# CH382CRD.net
KiCad netlist of a schematic drawn in Altium Designer
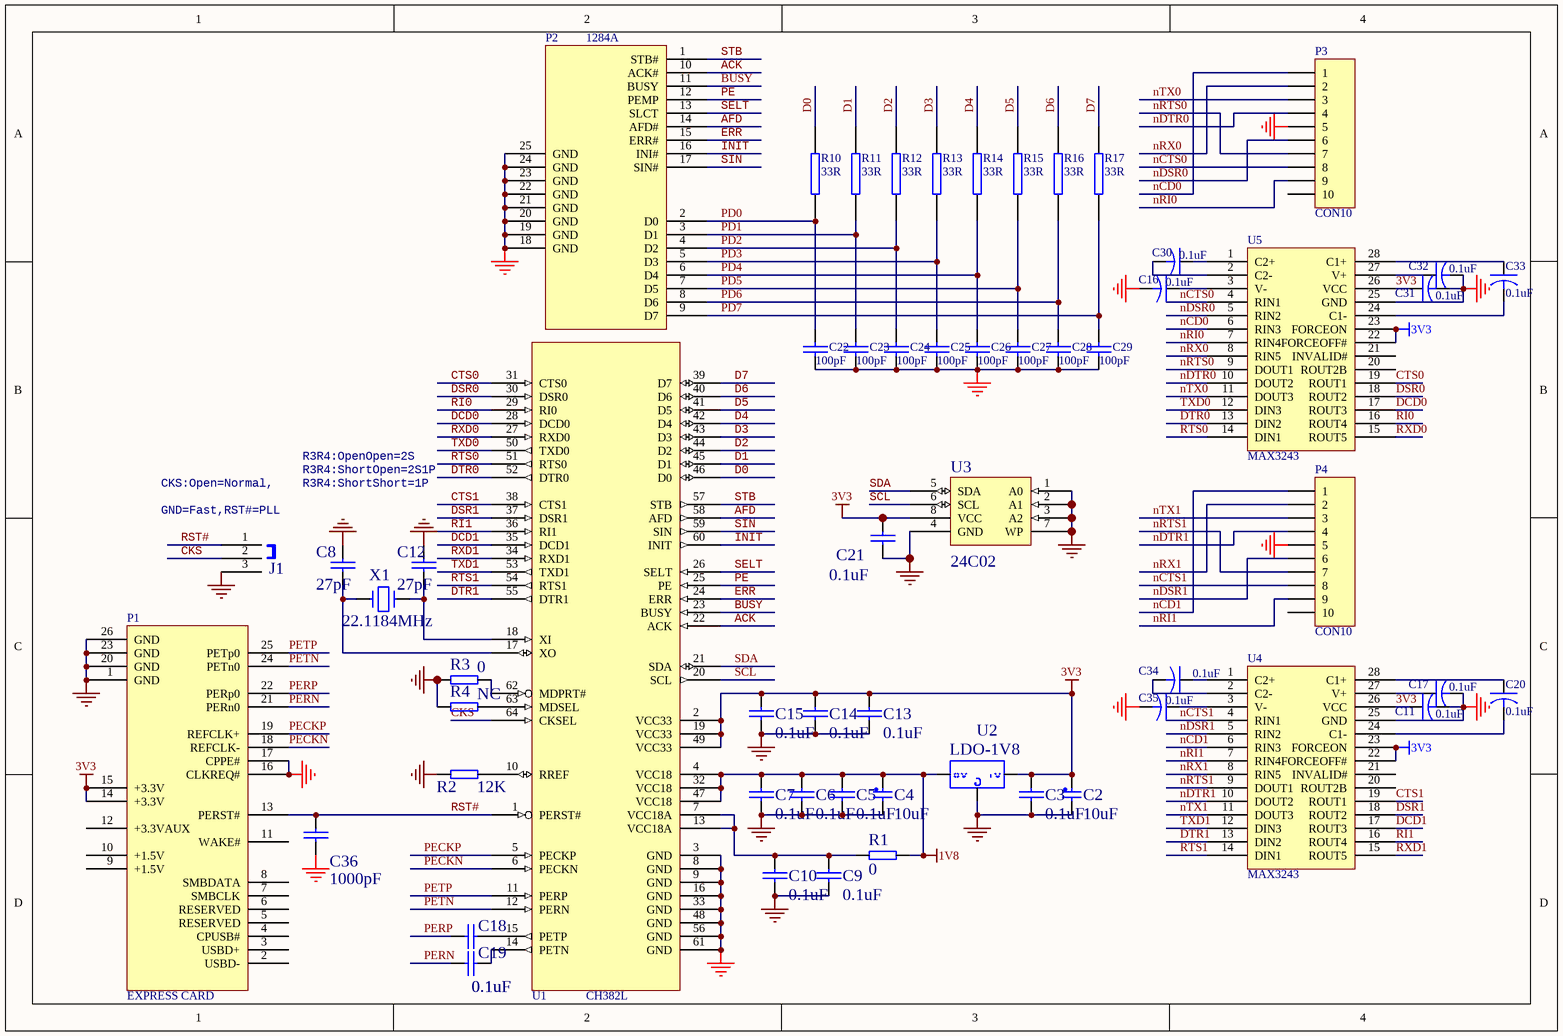
[diagram p0: CH382CRD.SchDoc]

(export (version "E")
  (design (tool "Eeschema 10.0.6"))
  (components
    (comp (ref "C2") (value "10uF") (footprint "3216") (libsource (lib "*") (part "Pro89C.tmp_10u_4")))
    (comp (ref "C3") (value "0.1uF") (footprint "0603") (libsource (lib "*") (part "Pro89C.tmp_0.1u_3")))
    (comp (ref "C4") (value "10uF") (footprint "3216") (libsource (lib "*") (part "Pro89C.tmp_10u_4")))
    (comp (ref "C5") (value "0.1uF") (footprint "0603") (libsource (lib "*") (part "Pro89C.tmp_0.1u_3")))
    (comp (ref "C6") (value "0.1uF") (footprint "0603") (libsource (lib "*") (part "Pro89C.tmp_0.1u_3")))
    (comp (ref "C7") (value "0.1uF") (footprint "0603") (libsource (lib "*") (part "Pro89C.tmp_0.1u_3")))
    (comp (ref "C8") (value "27pF") (footprint "0603") (libsource (lib "*") (part "Pro5B1.tmp_27p_3")))
    (comp (ref "C9") (value "0.1uF") (footprint "0603") (libsource (lib "*") (part "Pro89C.tmp_0.1u_3")))
    (comp (ref "C10") (value "0.1uF") (footprint "0603") (libsource (lib "*") (part "Pro89C.tmp_0.1u_3")))
    (comp (ref "C11")
      (value "0.1uF")
      (footprint "0603")
      (description "Capacitor")
      (libsource (lib "*") (part "CAPACITOR"))
    )
    (comp (ref "C12") (value "27pF") (footprint "0603") (libsource (lib "*") (part "Pro5B1.tmp_27p_3")))
    (comp (ref "C13") (value "0.1uF") (footprint "0603") (libsource (lib "*") (part "Pro89C.tmp_0.1u_3")))
    (comp (ref "C14") (value "0.1uF") (footprint "0603") (libsource (lib "*") (part "Pro89C.tmp_0.1u_3")))
    (comp (ref "C15") (value "0.1uF") (footprint "0603") (libsource (lib "*") (part "Pro89C.tmp_0.1u_3")))
    (comp (ref "C16")
      (value "0.1uF")
      (footprint "0603")
      (description "Capacitor")
      (libsource (lib "*") (part "CAPACITOR"))
    )
    (comp (ref "C17")
      (value "0.1uF")
      (footprint "0603")
      (description "Capacitor")
      (libsource (lib "*") (part "CAPACITOR"))
    )
    (comp (ref "C18") (value "0.1uF") (footprint "0603") (libsource (lib "*") (part "Pro89C.tmp_0.1u_70")))
    (comp (ref "C19") (value "0.1uF") (footprint "0603") (libsource (lib "*") (part "Pro89C.tmp_0.1u_71")))
    (comp (ref "C20")
      (value "0.1uF")
      (footprint "0603")
      (description "Capacitor")
      (libsource (lib "*") (part "CAPACITOR"))
    )
    (comp (ref "C21") (value "0.1uF") (footprint "0603") (libsource (lib "*") (part "Pro89C.tmp_0.1u_3")))
    (comp (ref "C22")
      (value "100pF")
      (footprint "0603")
      (description "Capacitor")
      (libsource (lib "*") (part "CAP"))
    )
    (comp (ref "C23")
      (value "100pF")
      (footprint "0603")
      (description "Capacitor")
      (libsource (lib "*") (part "CAP"))
    )
    (comp (ref "C24")
      (value "100pF")
      (footprint "0603")
      (description "Capacitor")
      (libsource (lib "*") (part "CAP"))
    )
    (comp (ref "C25")
      (value "100pF")
      (footprint "0603")
      (description "Capacitor")
      (libsource (lib "*") (part "CAP"))
    )
    (comp (ref "C26")
      (value "100pF")
      (footprint "0603")
      (description "Capacitor")
      (libsource (lib "*") (part "CAP"))
    )
    (comp (ref "C27")
      (value "100pF")
      (footprint "0603")
      (description "Capacitor")
      (libsource (lib "*") (part "CAP"))
    )
    (comp (ref "C28")
      (value "100pF")
      (footprint "0603")
      (description "Capacitor")
      (libsource (lib "*") (part "CAP"))
    )
    (comp (ref "C29")
      (value "100pF")
      (footprint "0603")
      (description "Capacitor")
      (libsource (lib "*") (part "CAP"))
    )
    (comp (ref "C30")
      (value "0.1uF")
      (footprint "0603")
      (description "Capacitor")
      (libsource (lib "*") (part "CAPACITOR"))
    )
    (comp (ref "C31")
      (value "0.1uF")
      (footprint "0603")
      (description "Capacitor")
      (libsource (lib "*") (part "CAPACITOR"))
    )
    (comp (ref "C32")
      (value "0.1uF")
      (footprint "0603")
      (description "Capacitor")
      (libsource (lib "*") (part "CAPACITOR"))
    )
    (comp (ref "C33")
      (value "0.1uF")
      (footprint "0603")
      (description "Capacitor")
      (libsource (lib "*") (part "CAPACITOR"))
    )
    (comp (ref "C34")
      (value "0.1uF")
      (footprint "0603")
      (description "Capacitor")
      (libsource (lib "*") (part "CAPACITOR"))
    )
    (comp (ref "C35")
      (value "0.1uF")
      (footprint "0603")
      (description "Capacitor")
      (libsource (lib "*") (part "CAPACITOR"))
    )
    (comp (ref "C36") (value "1000pF") (footprint "0603") (libsource (lib "*") (part "Pro5B1.tmp_27p_3")))
    (comp (ref "J1") (value "3JUMPS") (footprint "SIP3") (libsource (lib "*") (part "Pro5B1.tmp_3JUMPS_1")))
    (comp (ref "P1") (value "EXPRESS CARD") (libsource (lib "*") (part "EXPRESSCARD")))
    (comp (ref "P2") (value "1284A") (footprint "DB25RA/F") (libsource (lib "*") (part "1284A")))
    (comp (ref "P3")
      (value "CON10")
      (footprint "IDC10")
      (description "Connector")
      (libsource (lib "*") (part "CON10"))
    )
    (comp (ref "P4")
      (value "CON10")
      (footprint "IDC10")
      (description "Connector")
      (libsource (lib "*") (part "CON10"))
    )
    (comp (ref "R1") (value "0") (footprint "0805") (libsource (lib "*") (part "Pro89C.tmp_0_1")))
    (comp (ref "R2") (value "12K") (footprint "0603") (libsource (lib "*") (part "Pro5B1.tmp_12K_15")))
    (comp (ref "R3") (value "0") (footprint "0603") (libsource (lib "*") (part "Pro3F8.tmp_0_4")))
    (comp (ref "R4") (value "NC") (footprint "0603") (libsource (lib "*") (part "Pro3F8.tmp_0_4")))
    (comp (ref "R10") (value "33R") (footprint "0603") (libsource (lib "*") (part "RES2")))
    (comp (ref "R11") (value "33R") (footprint "0603") (libsource (lib "*") (part "RES2")))
    (comp (ref "R12") (value "33R") (footprint "0603") (libsource (lib "*") (part "RES2")))
    (comp (ref "R13") (value "33R") (footprint "0603") (libsource (lib "*") (part "RES2")))
    (comp (ref "R14") (value "33R") (footprint "0603") (libsource (lib "*") (part "RES2")))
    (comp (ref "R15") (value "33R") (footprint "0603") (libsource (lib "*") (part "RES2")))
    (comp (ref "R16") (value "33R") (footprint "0603") (libsource (lib "*") (part "RES2")))
    (comp (ref "R17") (value "33R") (footprint "0603") (libsource (lib "*") (part "RES2")))
    (comp (ref "U1")
      (value "CH382L")
      (footprint "LQFP64")
      (description "PCIe to 2S1P: Print Port / Parallel and Dual 16C550 UART with 256 byte FIFO")
      (libsource (lib "*") (part "CH382L"))
    )
    (comp (ref "U2")
      (value "LDO-1V8")
      (footprint "SOT-223")
      (libsource (lib "*") (part "Pro89C.tmp_LDO-1V8_68"))
    )
    (comp (ref "U3") (value "24C02") (footprint "SOP8") (libsource (lib "*") (part "Pro89C.tmp_24C02_11")))
    (comp (ref "U4") (value "MAX3243") (footprint "SSOP28") (libsource (lib "*") (part "MAX3243")))
    (comp (ref "U5") (value "MAX3243") (footprint "SSOP28") (libsource (lib "*") (part "MAX3243")))
    (comp (ref "X1")
      (value "22.1184MHz")
      (footprint "XTAL62/28")
      (libsource (lib "*") (part "Pro5B1.tmp_22.1184MHz_4"))
    )
  )
  (nets
    (net (code "1") (name "/ACK") (class "Default")
      (node (ref "P2") (pin "10") (pinfunction "ACK#_10") (pintype "passive"))
      (node (ref "U1") (pin "22") (pinfunction "ACK_22") (pintype "input"))
    )
    (net (code "2") (name "/AFD") (class "Default")
      (node (ref "P2") (pin "14") (pinfunction "AFD#_14") (pintype "passive"))
      (node (ref "U1") (pin "58") (pinfunction "AFD_58") (pintype "output"))
    )
    (net (code "3") (name "/BUSY") (class "Default")
      (node (ref "P2") (pin "11") (pinfunction "BUSY_11") (pintype "passive"))
      (node (ref "U1") (pin "23") (pinfunction "BUSY_23") (pintype "input"))
    )
    (net (code "4") (name "/CKS") (class "Default")
      (node (ref "J1") (pin "2") (pintype "passive"))
      (node (ref "U1") (pin "64") (pinfunction "CKSEL_64") (pintype "input"))
    )
    (net (code "5") (name "/CTS0") (class "Default")
      (node (ref "U1") (pin "31") (pinfunction "CTS0_31") (pintype "input"))
      (node (ref "U5") (pin "19") (pinfunction "ROUT1_19") (pintype "passive"))
    )
    (net (code "6") (name "/CTS1") (class "Default")
      (node (ref "U1") (pin "38") (pinfunction "CTS1_38") (pintype "input"))
      (node (ref "U4") (pin "19") (pinfunction "ROUT1_19") (pintype "passive"))
    )
    (net (code "7") (name "/D0") (class "Default")
      (node (ref "R10") (pin "2") (pinfunction "2_2") (pintype "passive"))
      (node (ref "U1") (pin "46") (pinfunction "D0_46") (pintype "bidirectional"))
    )
    (net (code "8") (name "/D1") (class "Default")
      (node (ref "R11") (pin "2") (pinfunction "2_2") (pintype "passive"))
      (node (ref "U1") (pin "45") (pinfunction "D1_45") (pintype "bidirectional"))
    )
    (net (code "9") (name "/D2") (class "Default")
      (node (ref "R12") (pin "2") (pinfunction "2_2") (pintype "passive"))
      (node (ref "U1") (pin "44") (pinfunction "D2_44") (pintype "bidirectional"))
    )
    (net (code "10") (name "/D3") (class "Default")
      (node (ref "R13") (pin "2") (pinfunction "2_2") (pintype "passive"))
      (node (ref "U1") (pin "43") (pinfunction "D3_43") (pintype "bidirectional"))
    )
    (net (code "11") (name "/D4") (class "Default")
      (node (ref "R14") (pin "2") (pinfunction "2_2") (pintype "passive"))
      (node (ref "U1") (pin "42") (pinfunction "D4_42") (pintype "bidirectional"))
    )
    (net (code "12") (name "/D5") (class "Default")
      (node (ref "R15") (pin "2") (pinfunction "2_2") (pintype "passive"))
      (node (ref "U1") (pin "41") (pinfunction "D5_41") (pintype "bidirectional"))
    )
    (net (code "13") (name "/D6") (class "Default")
      (node (ref "R16") (pin "2") (pinfunction "2_2") (pintype "passive"))
      (node (ref "U1") (pin "40") (pinfunction "D6_40") (pintype "bidirectional"))
    )
    (net (code "14") (name "/D7") (class "Default")
      (node (ref "R17") (pin "2") (pinfunction "2_2") (pintype "passive"))
      (node (ref "U1") (pin "39") (pinfunction "D7_39") (pintype "bidirectional"))
    )
    (net (code "15") (name "/DCD0") (class "Default")
      (node (ref "U1") (pin "28") (pinfunction "DCD0_28") (pintype "input"))
      (node (ref "U5") (pin "17") (pinfunction "ROUT3_17") (pintype "passive"))
    )
    (net (code "16") (name "/DCD1") (class "Default")
      (node (ref "U1") (pin "35") (pinfunction "DCD1_35") (pintype "input"))
      (node (ref "U4") (pin "17") (pinfunction "ROUT3_17") (pintype "passive"))
    )
    (net (code "17") (name "/DSR0") (class "Default")
      (node (ref "U1") (pin "30") (pinfunction "DSR0_30") (pintype "input"))
      (node (ref "U5") (pin "18") (pinfunction "ROUT2_18") (pintype "passive"))
    )
    (net (code "18") (name "/DSR1") (class "Default")
      (node (ref "U1") (pin "37") (pinfunction "DSR1_37") (pintype "input"))
      (node (ref "U4") (pin "18") (pinfunction "ROUT2_18") (pintype "passive"))
    )
    (net (code "19") (name "/DTR0") (class "Default")
      (node (ref "U1") (pin "52") (pinfunction "DTR0_52") (pintype "output"))
      (node (ref "U5") (pin "13") (pinfunction "DIN2_13") (pintype "passive"))
    )
    (net (code "20") (name "/DTR1") (class "Default")
      (node (ref "U1") (pin "55") (pinfunction "DTR1_55") (pintype "output"))
      (node (ref "U4") (pin "13") (pinfunction "DIN2_13") (pintype "passive"))
    )
    (net (code "21") (name "/ERR") (class "Default")
      (node (ref "P2") (pin "15") (pinfunction "ERR#_15") (pintype "passive"))
      (node (ref "U1") (pin "24") (pinfunction "ERR_24") (pintype "input"))
    )
    (net (code "22") (name "/INIT") (class "Default")
      (node (ref "P2") (pin "16") (pinfunction "INI#_16") (pintype "passive"))
      (node (ref "U1") (pin "60") (pinfunction "INIT_60") (pintype "output"))
    )
    (net (code "23") (name "/PD0") (class "Default")
      (node (ref "C22") (pin "1") (pinfunction "1_1") (pintype "passive"))
      (node (ref "P2") (pin "2") (pinfunction "D0_2") (pintype "passive"))
      (node (ref "R10") (pin "1") (pinfunction "1_1") (pintype "passive"))
    )
    (net (code "24") (name "/PD1") (class "Default")
      (node (ref "C23") (pin "1") (pinfunction "1_1") (pintype "passive"))
      (node (ref "P2") (pin "3") (pinfunction "D1_3") (pintype "passive"))
      (node (ref "R11") (pin "1") (pinfunction "1_1") (pintype "passive"))
    )
    (net (code "25") (name "/PD2") (class "Default")
      (node (ref "C24") (pin "1") (pinfunction "1_1") (pintype "passive"))
      (node (ref "P2") (pin "4") (pinfunction "D2_4") (pintype "passive"))
      (node (ref "R12") (pin "1") (pinfunction "1_1") (pintype "passive"))
    )
    (net (code "26") (name "/PD3") (class "Default")
      (node (ref "C25") (pin "1") (pinfunction "1_1") (pintype "passive"))
      (node (ref "P2") (pin "5") (pinfunction "D3_5") (pintype "passive"))
      (node (ref "R13") (pin "1") (pinfunction "1_1") (pintype "passive"))
    )
    (net (code "27") (name "/PD4") (class "Default")
      (node (ref "C26") (pin "1") (pinfunction "1_1") (pintype "passive"))
      (node (ref "P2") (pin "6") (pinfunction "D4_6") (pintype "passive"))
      (node (ref "R14") (pin "1") (pinfunction "1_1") (pintype "passive"))
    )
    (net (code "28") (name "/PD5") (class "Default")
      (node (ref "C27") (pin "1") (pinfunction "1_1") (pintype "passive"))
      (node (ref "P2") (pin "7") (pinfunction "D5_7") (pintype "passive"))
      (node (ref "R15") (pin "1") (pinfunction "1_1") (pintype "passive"))
    )
    (net (code "29") (name "/PD6") (class "Default")
      (node (ref "C28") (pin "1") (pinfunction "1_1") (pintype "passive"))
      (node (ref "P2") (pin "8") (pinfunction "D6_8") (pintype "passive"))
      (node (ref "R16") (pin "1") (pinfunction "1_1") (pintype "passive"))
    )
    (net (code "30") (name "/PD7") (class "Default")
      (node (ref "C29") (pin "1") (pinfunction "1_1") (pintype "passive"))
      (node (ref "P2") (pin "9") (pinfunction "D7_9") (pintype "passive"))
      (node (ref "R17") (pin "1") (pinfunction "1_1") (pintype "passive"))
    )
    (net (code "31") (name "/PE") (class "Default")
      (node (ref "P2") (pin "12") (pinfunction "PEMP_12") (pintype "passive"))
      (node (ref "U1") (pin "25") (pinfunction "PE_25") (pintype "input"))
    )
    (net (code "32") (name "/PECKN") (class "Default")
      (node (ref "P1") (pin "18") (pinfunction "REFCLK-_18") (pintype "passive"))
      (node (ref "U1") (pin "6") (pinfunction "PECKN_6") (pintype "input"))
    )
    (net (code "33") (name "/PECKP") (class "Default")
      (node (ref "P1") (pin "19") (pinfunction "REFCLK+_19") (pintype "passive"))
      (node (ref "U1") (pin "5") (pinfunction "PECKP_5") (pintype "input"))
    )
    (net (code "34") (name "/PERN") (class "Default")
      (node (ref "C19") (pin "1") (pintype "passive"))
      (node (ref "P1") (pin "21") (pinfunction "PERn0_21") (pintype "passive"))
    )
    (net (code "35") (name "/PERP") (class "Default")
      (node (ref "C18") (pin "1") (pintype "passive"))
      (node (ref "P1") (pin "22") (pinfunction "PERp0_22") (pintype "passive"))
    )
    (net (code "36") (name "/PETN") (class "Default")
      (node (ref "P1") (pin "24") (pinfunction "PETn0_24") (pintype "passive"))
      (node (ref "U1") (pin "12") (pinfunction "PERN_12") (pintype "input"))
    )
    (net (code "37") (name "/PETP") (class "Default")
      (node (ref "P1") (pin "25") (pinfunction "PETp0_25") (pintype "passive"))
      (node (ref "U1") (pin "11") (pinfunction "PERP_11") (pintype "input"))
    )
    (net (code "38") (name "/RI0") (class "Default")
      (node (ref "U1") (pin "29") (pinfunction "RI0_29") (pintype "input"))
      (node (ref "U5") (pin "16") (pinfunction "ROUT4_16") (pintype "passive"))
    )
    (net (code "39") (name "/RI1") (class "Default")
      (node (ref "U1") (pin "36") (pinfunction "RI1_36") (pintype "input"))
      (node (ref "U4") (pin "16") (pinfunction "ROUT4_16") (pintype "passive"))
    )
    (net (code "40") (name "/RST#") (class "Default")
      (node (ref "C36") (pin "1") (pintype "passive"))
      (node (ref "J1") (pin "1") (pintype "passive"))
      (node (ref "P1") (pin "13") (pinfunction "PERST#_13") (pintype "passive"))
      (node (ref "U1") (pin "1") (pinfunction "PERST#_1") (pintype "input"))
    )
    (net (code "41") (name "/RTS0") (class "Default")
      (node (ref "U1") (pin "51") (pinfunction "RTS0_51") (pintype "output"))
      (node (ref "U5") (pin "14") (pinfunction "DIN1_14") (pintype "passive"))
    )
    (net (code "42") (name "/RTS1") (class "Default")
      (node (ref "U1") (pin "54") (pinfunction "RTS1_54") (pintype "output"))
      (node (ref "U4") (pin "14") (pinfunction "DIN1_14") (pintype "passive"))
    )
    (net (code "43") (name "/RXD0") (class "Default")
      (node (ref "U1") (pin "27") (pinfunction "RXD0_27") (pintype "input"))
      (node (ref "U5") (pin "15") (pinfunction "ROUT5_15") (pintype "passive"))
    )
    (net (code "44") (name "/RXD1") (class "Default")
      (node (ref "U1") (pin "34") (pinfunction "RXD1_34") (pintype "input"))
      (node (ref "U4") (pin "15") (pinfunction "ROUT5_15") (pintype "passive"))
    )
    (net (code "45") (name "/SCL") (class "Default")
      (node (ref "U1") (pin "20") (pinfunction "SCL_20") (pintype "output"))
      (node (ref "U3") (pin "6") (pinfunction "SCL_6") (pintype "bidirectional"))
    )
    (net (code "46") (name "/SDA") (class "Default")
      (node (ref "U1") (pin "21") (pinfunction "SDA_21") (pintype "bidirectional"))
      (node (ref "U3") (pin "5") (pinfunction "SDA_5") (pintype "bidirectional"))
    )
    (net (code "47") (name "/SELT") (class "Default")
      (node (ref "P2") (pin "13") (pinfunction "SLCT_13") (pintype "passive"))
      (node (ref "U1") (pin "26") (pinfunction "SELT_26") (pintype "input"))
    )
    (net (code "48") (name "/SIN") (class "Default")
      (node (ref "P2") (pin "17") (pinfunction "SIN#_17") (pintype "passive"))
      (node (ref "U1") (pin "59") (pinfunction "SIN_59") (pintype "output"))
    )
    (net (code "49") (name "/STB") (class "Default")
      (node (ref "P2") (pin "1") (pinfunction "STB#_1") (pintype "passive"))
      (node (ref "U1") (pin "57") (pinfunction "STB_57") (pintype "output"))
    )
    (net (code "50") (name "/TXD0") (class "Default")
      (node (ref "U1") (pin "50") (pinfunction "TXD0_50") (pintype "output"))
      (node (ref "U5") (pin "12") (pinfunction "DIN3_12") (pintype "passive"))
    )
    (net (code "51") (name "/TXD1") (class "Default")
      (node (ref "U1") (pin "53") (pinfunction "TXD1_53") (pintype "output"))
      (node (ref "U4") (pin "12") (pinfunction "DIN3_12") (pintype "passive"))
    )
    (net (code "52") (name "/nCD0") (class "Default")
      (node (ref "P3") (pin "1") (pinfunction "1_1") (pintype "passive"))
      (node (ref "U5") (pin "6") (pinfunction "RIN3_6") (pintype "passive"))
    )
    (net (code "53") (name "/nCD1") (class "Default")
      (node (ref "P4") (pin "1") (pinfunction "1_1") (pintype "passive"))
      (node (ref "U4") (pin "6") (pinfunction "RIN3_6") (pintype "passive"))
    )
    (net (code "54") (name "/nCTS0") (class "Default")
      (node (ref "P3") (pin "8") (pinfunction "8_8") (pintype "passive"))
      (node (ref "U5") (pin "4") (pinfunction "RIN1_4") (pintype "passive"))
    )
    (net (code "55") (name "/nCTS1") (class "Default")
      (node (ref "P4") (pin "8") (pinfunction "8_8") (pintype "passive"))
      (node (ref "U4") (pin "4") (pinfunction "RIN1_4") (pintype "passive"))
    )
    (net (code "56") (name "/nDSR0") (class "Default")
      (node (ref "P3") (pin "6") (pinfunction "6_6") (pintype "passive"))
      (node (ref "U5") (pin "5") (pinfunction "RIN2_5") (pintype "passive"))
    )
    (net (code "57") (name "/nDSR1") (class "Default")
      (node (ref "P4") (pin "6") (pinfunction "6_6") (pintype "passive"))
      (node (ref "U4") (pin "5") (pinfunction "RIN2_5") (pintype "passive"))
    )
    (net (code "58") (name "/nDTR0") (class "Default")
      (node (ref "P3") (pin "4") (pinfunction "4_4") (pintype "passive"))
      (node (ref "U5") (pin "10") (pinfunction "DOUT2_10") (pintype "passive"))
    )
    (net (code "59") (name "/nDTR1") (class "Default")
      (node (ref "P4") (pin "4") (pinfunction "4_4") (pintype "passive"))
      (node (ref "U4") (pin "10") (pinfunction "DOUT2_10") (pintype "passive"))
    )
    (net (code "60") (name "/nRI0") (class "Default")
      (node (ref "P3") (pin "9") (pinfunction "9_9") (pintype "passive"))
      (node (ref "U5") (pin "7") (pinfunction "RIN4_7") (pintype "passive"))
    )
    (net (code "61") (name "/nRI1") (class "Default")
      (node (ref "P4") (pin "9") (pinfunction "9_9") (pintype "passive"))
      (node (ref "U4") (pin "7") (pinfunction "RIN4_7") (pintype "passive"))
    )
    (net (code "62") (name "/nRTS0") (class "Default")
      (node (ref "P3") (pin "7") (pinfunction "7_7") (pintype "passive"))
      (node (ref "U5") (pin "9") (pinfunction "DOUT1_9") (pintype "passive"))
    )
    (net (code "63") (name "/nRTS1") (class "Default")
      (node (ref "P4") (pin "7") (pinfunction "7_7") (pintype "passive"))
      (node (ref "U4") (pin "9") (pinfunction "DOUT1_9") (pintype "passive"))
    )
    (net (code "64") (name "/nRX0") (class "Default")
      (node (ref "P3") (pin "2") (pinfunction "2_2") (pintype "passive"))
      (node (ref "U5") (pin "8") (pinfunction "RIN5_8") (pintype "passive"))
    )
    (net (code "65") (name "/nRX1") (class "Default")
      (node (ref "P4") (pin "2") (pinfunction "2_2") (pintype "passive"))
      (node (ref "U4") (pin "8") (pinfunction "RIN5_8") (pintype "passive"))
    )
    (net (code "66") (name "/nTX0") (class "Default")
      (node (ref "P3") (pin "3") (pinfunction "3_3") (pintype "passive"))
      (node (ref "U5") (pin "11") (pinfunction "DOUT3_11") (pintype "passive"))
    )
    (net (code "67") (name "/nTX1") (class "Default")
      (node (ref "P4") (pin "3") (pinfunction "3_3") (pintype "passive"))
      (node (ref "U4") (pin "11") (pinfunction "DOUT3_11") (pintype "passive"))
    )
    (net (code "68") (name "1V8") (class "Default")
      (node (ref "C4") (pin "1") (pintype "passive"))
      (node (ref "C5") (pin "1") (pintype "passive"))
      (node (ref "C6") (pin "1") (pintype "passive"))
      (node (ref "C7") (pin "1") (pintype "passive"))
      (node (ref "R1") (pin "1") (pintype "passive"))
      (node (ref "U1") (pin "32") (pinfunction "VCC18_32") (pintype "power_in"))
      (node (ref "U1") (pin "4") (pinfunction "VCC18_4") (pintype "power_in"))
      (node (ref "U1") (pin "47") (pinfunction "VCC18_47") (pintype "power_in"))
      (node (ref "U2") (pin "2") (pintype "passive"))
    )
    (net (code "69") (name "3V3") (class "Default")
      (node (ref "C11") (pin "1") (pinfunction "1_1") (pintype "passive"))
      (node (ref "C13") (pin "1") (pintype "passive"))
      (node (ref "C14") (pin "1") (pintype "passive"))
      (node (ref "C15") (pin "1") (pintype "passive"))
      (node (ref "C2") (pin "1") (pintype "passive"))
      (node (ref "C21") (pin "1") (pintype "passive"))
      (node (ref "C3") (pin "1") (pintype "passive"))
      (node (ref "C31") (pin "1") (pinfunction "1_1") (pintype "passive"))
      (node (ref "P1") (pin "14") (pinfunction "+3.3V_14") (pintype "passive"))
      (node (ref "P1") (pin "15") (pinfunction "+3.3V_15") (pintype "passive"))
      (node (ref "U1") (pin "19") (pinfunction "VCC33_19") (pintype "power_in"))
      (node (ref "U1") (pin "2") (pinfunction "VCC33_2") (pintype "power_in"))
      (node (ref "U1") (pin "49") (pinfunction "VCC33_49") (pintype "power_in"))
      (node (ref "U2") (pin "3") (pintype "passive"))
      (node (ref "U3") (pin "8") (pinfunction "VCC_8") (pintype "power_in"))
      (node (ref "U4") (pin "22") (pinfunction "FORCEOFF#_22") (pintype "passive"))
      (node (ref "U4") (pin "23") (pinfunction "FORCEON_23") (pintype "passive"))
      (node (ref "U4") (pin "26") (pinfunction "VCC_26") (pintype "passive"))
      (node (ref "U5") (pin "22") (pinfunction "FORCEOFF#_22") (pintype "passive"))
      (node (ref "U5") (pin "23") (pinfunction "FORCEON_23") (pintype "passive"))
      (node (ref "U5") (pin "26") (pinfunction "VCC_26") (pintype "passive"))
    )
    (net (code "70") (name "GND") (class "Default")
      (node (ref "C10") (pin "2") (pintype "passive"))
      (node (ref "C11") (pin "2") (pinfunction "2_2") (pintype "passive"))
      (node (ref "C12") (pin "2") (pintype "passive"))
      (node (ref "C13") (pin "2") (pintype "passive"))
      (node (ref "C14") (pin "2") (pintype "passive"))
      (node (ref "C15") (pin "2") (pintype "passive"))
      (node (ref "C16") (pin "2") (pinfunction "2_2") (pintype "passive"))
      (node (ref "C17") (pin "2") (pinfunction "2_2") (pintype "passive"))
      (node (ref "C2") (pin "2") (pintype "passive"))
      (node (ref "C21") (pin "2") (pintype "passive"))
      (node (ref "C22") (pin "2") (pinfunction "2_2") (pintype "passive"))
      (node (ref "C23") (pin "2") (pinfunction "2_2") (pintype "passive"))
      (node (ref "C24") (pin "2") (pinfunction "2_2") (pintype "passive"))
      (node (ref "C25") (pin "2") (pinfunction "2_2") (pintype "passive"))
      (node (ref "C26") (pin "2") (pinfunction "2_2") (pintype "passive"))
      (node (ref "C27") (pin "2") (pinfunction "2_2") (pintype "passive"))
      (node (ref "C28") (pin "2") (pinfunction "2_2") (pintype "passive"))
      (node (ref "C29") (pin "2") (pinfunction "2_2") (pintype "passive"))
      (node (ref "C3") (pin "2") (pintype "passive"))
      (node (ref "C31") (pin "2") (pinfunction "2_2") (pintype "passive"))
      (node (ref "C32") (pin "2") (pinfunction "2_2") (pintype "passive"))
      (node (ref "C35") (pin "2") (pinfunction "2_2") (pintype "passive"))
      (node (ref "C36") (pin "2") (pintype "passive"))
      (node (ref "C4") (pin "2") (pintype "passive"))
      (node (ref "C5") (pin "2") (pintype "passive"))
      (node (ref "C6") (pin "2") (pintype "passive"))
      (node (ref "C7") (pin "2") (pintype "passive"))
      (node (ref "C8") (pin "2") (pintype "passive"))
      (node (ref "C9") (pin "2") (pintype "passive"))
      (node (ref "J1") (pin "3") (pintype "passive"))
      (node (ref "P1") (pin "1") (pinfunction "GND_1") (pintype "passive"))
      (node (ref "P1") (pin "16") (pinfunction "CLKREQ#_16") (pintype "passive"))
      (node (ref "P1") (pin "17") (pinfunction "CPPE#_17") (pintype "passive"))
      (node (ref "P1") (pin "20") (pinfunction "GND_20") (pintype "passive"))
      (node (ref "P1") (pin "23") (pinfunction "GND_23") (pintype "passive"))
      (node (ref "P1") (pin "26") (pinfunction "GND_26") (pintype "passive"))
      (node (ref "P2") (pin "18") (pinfunction "GND_18") (pintype "passive"))
      (node (ref "P2") (pin "19") (pinfunction "GND_19") (pintype "passive"))
      (node (ref "P2") (pin "20") (pinfunction "GND_20") (pintype "passive"))
      (node (ref "P2") (pin "21") (pinfunction "GND_21") (pintype "passive"))
      (node (ref "P2") (pin "22") (pinfunction "GND_22") (pintype "passive"))
      (node (ref "P2") (pin "23") (pinfunction "GND_23") (pintype "passive"))
      (node (ref "P2") (pin "24") (pinfunction "GND_24") (pintype "passive"))
      (node (ref "P2") (pin "25") (pinfunction "GND_25") (pintype "passive"))
      (node (ref "P3") (pin "5") (pinfunction "5_5") (pintype "passive"))
      (node (ref "P4") (pin "5") (pinfunction "5_5") (pintype "passive"))
      (node (ref "R2") (pin "1") (pintype "passive"))
      (node (ref "R3") (pin "2") (pintype "passive"))
      (node (ref "R4") (pin "2") (pintype "passive"))
      (node (ref "U1") (pin "16") (pinfunction "GND_16") (pintype "power_in"))
      (node (ref "U1") (pin "3") (pinfunction "GND_3") (pintype "power_in"))
      (node (ref "U1") (pin "33") (pinfunction "GND_33") (pintype "power_in"))
      (node (ref "U1") (pin "48") (pinfunction "GND_48") (pintype "power_in"))
      (node (ref "U1") (pin "56") (pinfunction "GND_56") (pintype "power_in"))
      (node (ref "U1") (pin "61") (pinfunction "GND_61") (pintype "power_in"))
      (node (ref "U1") (pin "8") (pinfunction "GND_8") (pintype "power_in"))
      (node (ref "U1") (pin "9") (pinfunction "GND_9") (pintype "power_in"))
      (node (ref "U2") (pin "1") (pintype "passive"))
      (node (ref "U3") (pin "1") (pinfunction "A0_1") (pintype "input"))
      (node (ref "U3") (pin "2") (pinfunction "A1_2") (pintype "input"))
      (node (ref "U3") (pin "3") (pinfunction "A2_3") (pintype "input"))
      (node (ref "U3") (pin "4") (pinfunction "GND_4") (pintype "power_in"))
      (node (ref "U3") (pin "7") (pinfunction "WP_7") (pintype "passive"))
      (node (ref "U4") (pin "25") (pinfunction "GND_25") (pintype "passive"))
      (node (ref "U5") (pin "25") (pinfunction "GND_25") (pintype "passive"))
    )
    (net (code "71") (name "Net-(C10-Pad1)") (class "Default")
      (node (ref "C10") (pin "1") (pintype "passive"))
      (node (ref "C9") (pin "1") (pintype "passive"))
      (node (ref "R1") (pin "2") (pintype "passive"))
      (node (ref "U1") (pin "13") (pinfunction "VCC18A_13") (pintype "power_in"))
      (node (ref "U1") (pin "7") (pinfunction "VCC18A_7") (pintype "power_in"))
    )
    (net (code "72") (name "Net-(U1-MDPRT#)") (class "Default")
      (node (ref "R3") (pin "1") (pintype "passive"))
      (node (ref "U1") (pin "62") (pinfunction "MDPRT#_62") (pintype "input"))
    )
    (net (code "73") (name "Net-(U1-MDSEL)") (class "Default")
      (node (ref "R4") (pin "1") (pintype "passive"))
      (node (ref "U1") (pin "63") (pinfunction "MDSEL_63") (pintype "input"))
    )
    (net (code "74") (name "Net-(U1-PETN)") (class "Default")
      (node (ref "C19") (pin "2") (pintype "passive"))
      (node (ref "U1") (pin "14") (pinfunction "PETN_14") (pintype "output"))
    )
    (net (code "75") (name "Net-(U1-PETP)") (class "Default")
      (node (ref "C18") (pin "2") (pintype "passive"))
      (node (ref "U1") (pin "15") (pinfunction "PETP_15") (pintype "output"))
    )
    (net (code "76") (name "Net-(U1-RREF)") (class "Default")
      (node (ref "R2") (pin "2") (pintype "passive"))
      (node (ref "U1") (pin "10") (pinfunction "RREF_10") (pintype "bidirectional"))
    )
    (net (code "77") (name "Net-(U1-XI)") (class "Default")
      (node (ref "C12") (pin "1") (pintype "passive"))
      (node (ref "U1") (pin "18") (pinfunction "XI_18") (pintype "input"))
      (node (ref "X1") (pin "1") (pintype "passive"))
    )
    (net (code "78") (name "Net-(U1-XO)") (class "Default")
      (node (ref "C8") (pin "1") (pintype "passive"))
      (node (ref "U1") (pin "17") (pinfunction "XO_17") (pintype "bidirectional"))
      (node (ref "X1") (pin "2") (pintype "passive"))
    )
    (net (code "79") (name "Net-(U4-C1+)") (class "Default")
      (node (ref "C20") (pin "1") (pinfunction "1_1") (pintype "passive"))
      (node (ref "U4") (pin "28") (pinfunction "C1+_28") (pintype "passive"))
    )
    (net (code "80") (name "Net-(U4-C1-)") (class "Default")
      (node (ref "C20") (pin "2") (pinfunction "2_2") (pintype "passive"))
      (node (ref "U4") (pin "24") (pinfunction "C1-_24") (pintype "passive"))
    )
    (net (code "81") (name "Net-(U4-C2+)") (class "Default")
      (node (ref "C34") (pin "1") (pinfunction "1_1") (pintype "passive"))
      (node (ref "U4") (pin "1") (pinfunction "C2+_1") (pintype "passive"))
    )
    (net (code "82") (name "Net-(U4-C2-)") (class "Default")
      (node (ref "C34") (pin "2") (pinfunction "2_2") (pintype "passive"))
      (node (ref "U4") (pin "2") (pinfunction "C2-_2") (pintype "passive"))
    )
    (net (code "83") (name "Net-(U4-V+)") (class "Default")
      (node (ref "C17") (pin "1") (pinfunction "1_1") (pintype "passive"))
      (node (ref "U4") (pin "27") (pinfunction "V+_27") (pintype "passive"))
    )
    (net (code "84") (name "Net-(U4-V-)") (class "Default")
      (node (ref "C35") (pin "1") (pinfunction "1_1") (pintype "passive"))
      (node (ref "U4") (pin "3") (pinfunction "V-_3") (pintype "passive"))
    )
    (net (code "85") (name "Net-(U5-C1+)") (class "Default")
      (node (ref "C33") (pin "1") (pinfunction "1_1") (pintype "passive"))
      (node (ref "U5") (pin "28") (pinfunction "C1+_28") (pintype "passive"))
    )
    (net (code "86") (name "Net-(U5-C1-)") (class "Default")
      (node (ref "C33") (pin "2") (pinfunction "2_2") (pintype "passive"))
      (node (ref "U5") (pin "24") (pinfunction "C1-_24") (pintype "passive"))
    )
    (net (code "87") (name "Net-(U5-C2+)") (class "Default")
      (node (ref "C30") (pin "1") (pinfunction "1_1") (pintype "passive"))
      (node (ref "U5") (pin "1") (pinfunction "C2+_1") (pintype "passive"))
    )
    (net (code "88") (name "Net-(U5-C2-)") (class "Default")
      (node (ref "C30") (pin "2") (pinfunction "2_2") (pintype "passive"))
      (node (ref "U5") (pin "2") (pinfunction "C2-_2") (pintype "passive"))
    )
    (net (code "89") (name "Net-(U5-V+)") (class "Default")
      (node (ref "C32") (pin "1") (pinfunction "1_1") (pintype "passive"))
      (node (ref "U5") (pin "27") (pinfunction "V+_27") (pintype "passive"))
    )
    (net (code "90") (name "Net-(U5-V-)") (class "Default")
      (node (ref "C16") (pin "1") (pinfunction "1_1") (pintype "passive"))
      (node (ref "U5") (pin "3") (pinfunction "V-_3") (pintype "passive"))
    )
    (net (code "91") (name "unconnected-(P1-+1.5V-Pad9)") (class "Default")
      (node (ref "P1") (pin "9") (pinfunction "+1.5V_9") (pintype "passive"))
    )
    (net (code "92") (name "unconnected-(P1-+1.5V-Pad10)") (class "Default")
      (node (ref "P1") (pin "10") (pinfunction "+1.5V_10") (pintype "passive"))
    )
    (net (code "93") (name "unconnected-(P1-+3.3VAUX-Pad12)") (class "Default")
      (node (ref "P1") (pin "12") (pinfunction "+3.3VAUX_12") (pintype "passive"))
    )
    (net (code "94") (name "unconnected-(P1-CPUSB#-Pad4)") (class "Default")
      (node (ref "P1") (pin "4") (pinfunction "CPUSB#_4") (pintype "passive"))
    )
    (net (code "95") (name "unconnected-(P1-RESERVED-Pad5)") (class "Default")
      (node (ref "P1") (pin "5") (pinfunction "RESERVED_5") (pintype "passive"))
    )
    (net (code "96") (name "unconnected-(P1-RESERVED-Pad6)") (class "Default")
      (node (ref "P1") (pin "6") (pinfunction "RESERVED_6") (pintype "passive"))
    )
    (net (code "97") (name "unconnected-(P1-SMBCLK-Pad7)") (class "Default")
      (node (ref "P1") (pin "7") (pinfunction "SMBCLK_7") (pintype "passive"))
    )
    (net (code "98") (name "unconnected-(P1-SMBDATA-Pad8)") (class "Default")
      (node (ref "P1") (pin "8") (pinfunction "SMBDATA_8") (pintype "passive"))
    )
    (net (code "99") (name "unconnected-(P1-USBD+-Pad3)") (class "Default")
      (node (ref "P1") (pin "3") (pinfunction "USBD+_3") (pintype "passive"))
    )
    (net (code "100") (name "unconnected-(P1-USBD--Pad2)") (class "Default")
      (node (ref "P1") (pin "2") (pinfunction "USBD-_2") (pintype "passive"))
    )
    (net (code "101") (name "unconnected-(P1-WAKE#-Pad11)") (class "Default")
      (node (ref "P1") (pin "11") (pinfunction "WAKE#_11") (pintype "passive"))
    )
    (net (code "102") (name "unconnected-(P3-Pad10)") (class "Default")
      (node (ref "P3") (pin "10") (pinfunction "10_10") (pintype "passive"))
    )
    (net (code "103") (name "unconnected-(P4-Pad10)") (class "Default")
      (node (ref "P4") (pin "10") (pinfunction "10_10") (pintype "passive"))
    )
    (net (code "104") (name "unconnected-(U4-INVALID#-Pad21)") (class "Default")
      (node (ref "U4") (pin "21") (pinfunction "INVALID#_21") (pintype "passive"))
    )
    (net (code "105") (name "unconnected-(U4-ROUT2B-Pad20)") (class "Default")
      (node (ref "U4") (pin "20") (pinfunction "ROUT2B_20") (pintype "passive"))
    )
    (net (code "106") (name "unconnected-(U5-INVALID#-Pad21)") (class "Default")
      (node (ref "U5") (pin "21") (pinfunction "INVALID#_21") (pintype "passive"))
    )
    (net (code "107") (name "unconnected-(U5-ROUT2B-Pad20)") (class "Default")
      (node (ref "U5") (pin "20") (pinfunction "ROUT2B_20") (pintype "passive"))
    )
  )
)
